# sb-sonata-usbrp.net
KiCad netlist of a schematic drawn in Altium Designer
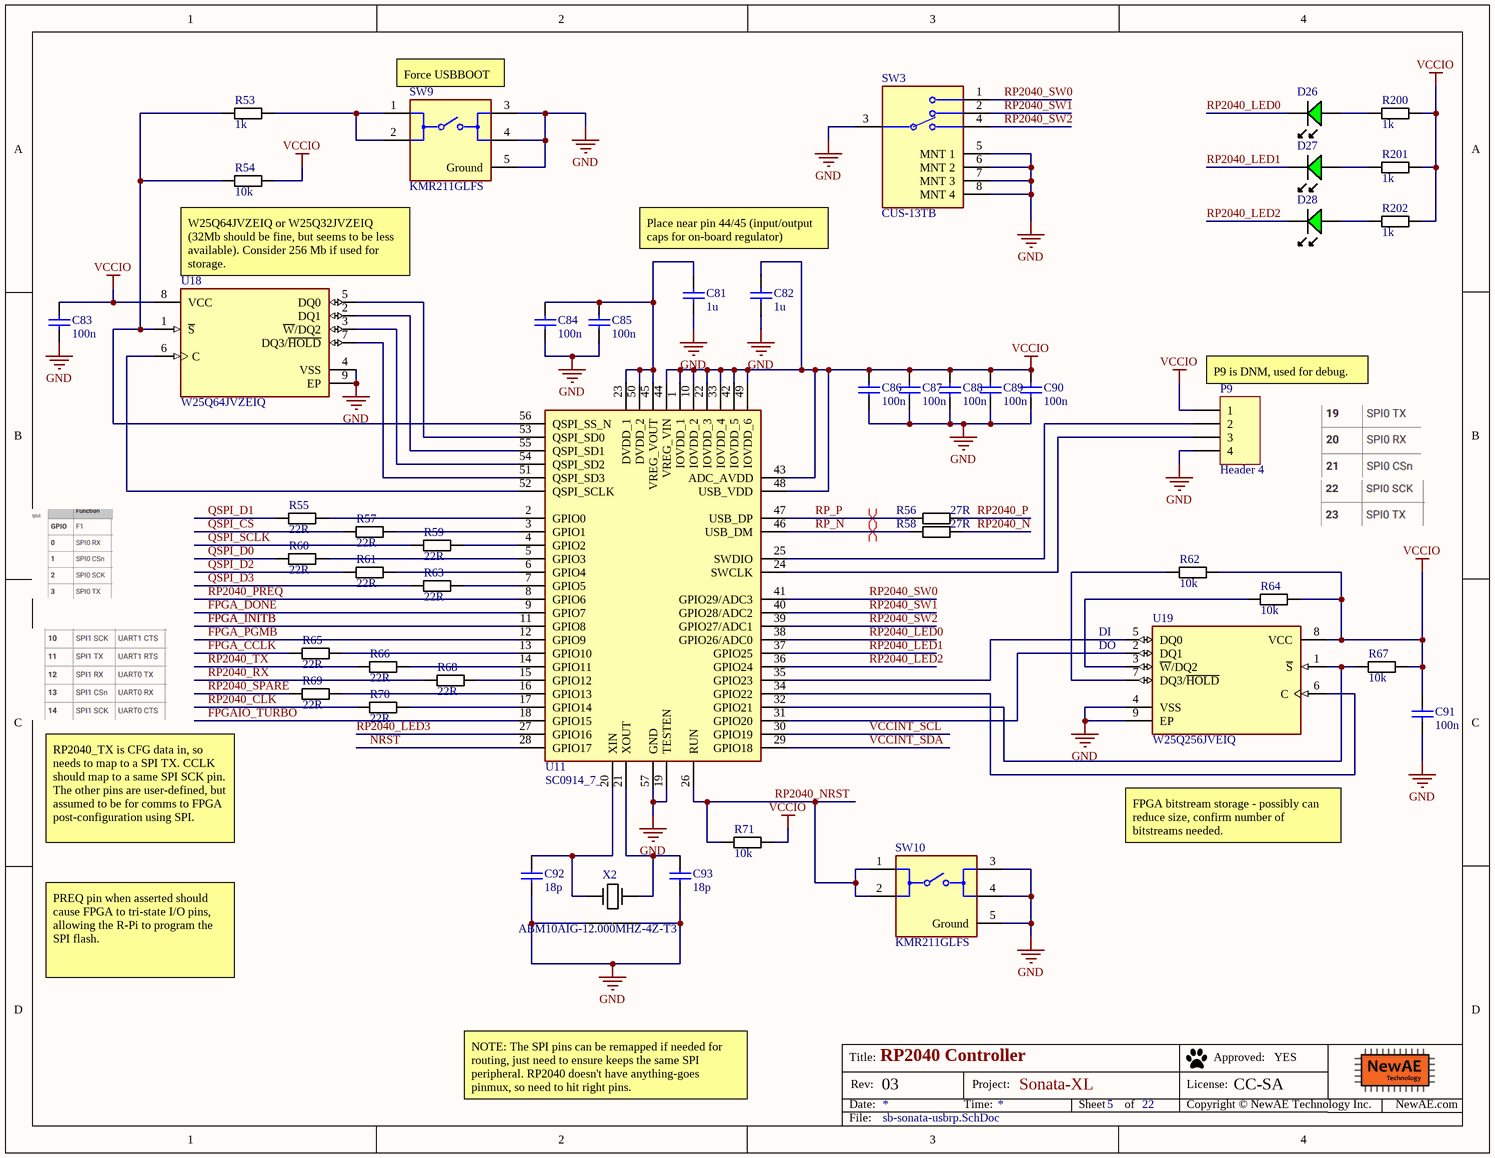
[diagram p0: sb-sonata-usbrp.SchDoc]

(export (version "E")
  (design (tool "Eeschema 10.0.6"))
  (components
    (comp (ref "C81")
      (value "1u")
      (footprint "CAPC0603_M")
      (description "1u, 0603, 50V")
      (fields (field (name "PART NUMBER") "CCHIP-1u-0603"))
      (libsource (lib "NewAE_AltiumLib") (part "CAP"))
    )
    (comp (ref "C82")
      (value "1u")
      (footprint "CAPC0603_M")
      (description "1u, 0603, 50V")
      (fields (field (name "PART NUMBER") "CCHIP-1u-0603"))
      (libsource (lib "NewAE_AltiumLib") (part "CAP"))
    )
    (comp (ref "C83")
      (value "100n")
      (footprint "CAPC0402_M")
      (description "100n, 0402")
      (fields (field (name "PART NUMBER") "CCHIP-100n-0402"))
      (libsource (lib "NewAE_AltiumLib") (part "CAP"))
    )
    (comp (ref "C84")
      (value "100n")
      (footprint "CAPC0402_M")
      (description "100n, 0402")
      (fields (field (name "PART NUMBER") "CCHIP-100n-0402"))
      (libsource (lib "NewAE_AltiumLib") (part "CAP"))
    )
    (comp (ref "C85")
      (value "100n")
      (footprint "CAPC0402_M")
      (description "100n, 0402")
      (fields (field (name "PART NUMBER") "CCHIP-100n-0402"))
      (libsource (lib "NewAE_AltiumLib") (part "CAP"))
    )
    (comp (ref "C86")
      (value "100n")
      (footprint "CAPC0402_M")
      (description "100n, 0402")
      (fields (field (name "PART NUMBER") "CCHIP-100n-0402"))
      (libsource (lib "NewAE_AltiumLib") (part "CAP"))
    )
    (comp (ref "C87")
      (value "100n")
      (footprint "CAPC0402_M")
      (description "100n, 0402")
      (fields (field (name "PART NUMBER") "CCHIP-100n-0402"))
      (libsource (lib "NewAE_AltiumLib") (part "CAP"))
    )
    (comp (ref "C88")
      (value "100n")
      (footprint "CAPC0402_M")
      (description "100n, 0402")
      (fields (field (name "PART NUMBER") "CCHIP-100n-0402"))
      (libsource (lib "NewAE_AltiumLib") (part "CAP"))
    )
    (comp (ref "C89")
      (value "100n")
      (footprint "CAPC0402_M")
      (description "100n, 0402")
      (fields (field (name "PART NUMBER") "CCHIP-100n-0402"))
      (libsource (lib "NewAE_AltiumLib") (part "CAP"))
    )
    (comp (ref "C90")
      (value "100n")
      (footprint "CAPC0402_M")
      (description "100n, 0402")
      (fields (field (name "PART NUMBER") "CCHIP-100n-0402"))
      (libsource (lib "NewAE_AltiumLib") (part "CAP"))
    )
    (comp (ref "C91")
      (value "100n")
      (footprint "CAPC0402_M")
      (description "100n, 0402")
      (fields (field (name "PART NUMBER") "CCHIP-100n-0402"))
      (libsource (lib "NewAE_AltiumLib") (part "CAP"))
    )
    (comp (ref "C92")
      (value "18p")
      (footprint "CAPC0402_M")
      (description "18p, 0402")
      (fields (field (name "PART NUMBER") "CCHIP-18p-0402"))
      (libsource (lib "NewAE_AltiumLib") (part "CAP"))
    )
    (comp (ref "C93")
      (value "18p")
      (footprint "CAPC0402_M")
      (description "18p, 0402")
      (fields (field (name "PART NUMBER") "CCHIP-18p-0402"))
      (libsource (lib "NewAE_AltiumLib") (part "CAP"))
    )
    (comp (ref "D26")
      (value "LED, 0603, Green")
      (footprint "LED-0603-GREEN")
      (description "Chip LED, Green")
      (fields (field (name "PART NUMBER") "LEDCHIP_0603_GREEN"))
      (libsource (lib "NewAE_AltiumLib") (part "LED_GREEN"))
    )
    (comp (ref "D27")
      (value "LED, 0603, Green")
      (footprint "LED-0603-GREEN")
      (description "Chip LED, Green")
      (fields (field (name "PART NUMBER") "LEDCHIP_0603_GREEN"))
      (libsource (lib "NewAE_AltiumLib") (part "LED_GREEN"))
    )
    (comp (ref "D28")
      (value "LED, 0603, Green")
      (footprint "LED-0603-GREEN")
      (description "Chip LED, Green")
      (fields (field (name "PART NUMBER") "LEDCHIP_0603_GREEN"))
      (libsource (lib "NewAE_AltiumLib") (part "LED_GREEN"))
    )
    (comp (ref "P9")
      (value "Header 4")
      (footprint "HDR1X4")
      (description "Header, 4-Pin")
      (fields (field (name "PUBLISHER") "Altium Limited"))
      (libsource (lib "Miscellaneous Connectors") (part "Header 4"))
    )
    (comp (ref "R53")
      (value "1k")
      (footprint "RESC1005X40N")
      (description "1k res, 0402, 1%, 1/16W")
      (fields (field (name "PART NUMBER") "RCHIP-1K-0402") (field (name "TOLERANCE") "1%"))
      (libsource (lib "NewAE_AltiumLib") (part "RES-EU"))
    )
    (comp (ref "R54")
      (value "10k")
      (footprint "RESC1005X40N")
      (description "10k res, 0402, 1%, 1/16W")
      (fields (field (name "PART NUMBER") "RCHIP-10K-0402") (field (name "TOLERANCE") "1%"))
      (libsource (lib "") (part "RES-EU_1"))
    )
    (comp (ref "R55")
      (value "22R")
      (footprint "RESC1005X40N")
      (description "22R res, 0402, 1%, 1/16W")
      (fields (field (name "PART NUMBER") "RCHIP-22R-0402") (field (name "TOLERANCE") "1%"))
      (libsource (lib "NewAE_AltiumLib") (part "RES-EU"))
    )
    (comp (ref "R56")
      (value "27R")
      (footprint "RESC1005X40N")
      (description "27R res, 0402, 1%, 1/16W")
      (fields (field (name "PART NUMBER") "RCHIP-27R-0402") (field (name "TOLERANCE") "1%"))
      (libsource (lib "") (part "RES-EU_1"))
    )
    (comp (ref "R57")
      (value "22R")
      (footprint "RESC1005X40N")
      (description "22R res, 0402, 1%, 1/16W")
      (fields (field (name "PART NUMBER") "RCHIP-22R-0402") (field (name "TOLERANCE") "1%"))
      (libsource (lib "NewAE_AltiumLib") (part "RES-EU"))
    )
    (comp (ref "R58")
      (value "27R")
      (footprint "RESC1005X40N")
      (description "27R res, 0402, 1%, 1/16W")
      (fields (field (name "PART NUMBER") "RCHIP-27R-0402") (field (name "TOLERANCE") "1%"))
      (libsource (lib "") (part "RES-EU_1"))
    )
    (comp (ref "R59")
      (value "22R")
      (footprint "RESC1005X40N")
      (description "22R res, 0402, 1%, 1/16W")
      (fields (field (name "PART NUMBER") "RCHIP-22R-0402") (field (name "TOLERANCE") "1%"))
      (libsource (lib "NewAE_AltiumLib") (part "RES-EU"))
    )
    (comp (ref "R60")
      (value "22R")
      (footprint "RESC1005X40N")
      (description "22R res, 0402, 1%, 1/16W")
      (fields (field (name "PART NUMBER") "RCHIP-22R-0402") (field (name "TOLERANCE") "1%"))
      (libsource (lib "NewAE_AltiumLib") (part "RES-EU"))
    )
    (comp (ref "R61")
      (value "22R")
      (footprint "RESC1005X40N")
      (description "22R res, 0402, 1%, 1/16W")
      (fields (field (name "PART NUMBER") "RCHIP-22R-0402") (field (name "TOLERANCE") "1%"))
      (libsource (lib "NewAE_AltiumLib") (part "RES-EU"))
    )
    (comp (ref "R62")
      (value "10k")
      (footprint "RESC1005X40N")
      (description "10k res, 0402, 1%, 1/16W")
      (fields (field (name "PART NUMBER") "RCHIP-10K-0402") (field (name "TOLERANCE") "1%"))
      (libsource (lib "") (part "RES-EU_1"))
    )
    (comp (ref "R63")
      (value "22R")
      (footprint "RESC1005X40N")
      (description "22R res, 0402, 1%, 1/16W")
      (fields (field (name "PART NUMBER") "RCHIP-22R-0402") (field (name "TOLERANCE") "1%"))
      (libsource (lib "NewAE_AltiumLib") (part "RES-EU"))
    )
    (comp (ref "R64")
      (value "10k")
      (footprint "RESC1005X40N")
      (description "10k res, 0402, 1%, 1/16W")
      (fields (field (name "PART NUMBER") "RCHIP-10K-0402") (field (name "TOLERANCE") "1%"))
      (libsource (lib "") (part "RES-EU_1"))
    )
    (comp (ref "R65")
      (value "22R")
      (footprint "RESC1005X40N")
      (description "22R res, 0402, 1%, 1/16W")
      (fields (field (name "PART NUMBER") "RCHIP-22R-0402") (field (name "TOLERANCE") "1%"))
      (libsource (lib "NewAE_AltiumLib") (part "RES-EU"))
    )
    (comp (ref "R66")
      (value "22R")
      (footprint "RESC1005X40N")
      (description "22R res, 0402, 1%, 1/16W")
      (fields (field (name "PART NUMBER") "RCHIP-22R-0402") (field (name "TOLERANCE") "1%"))
      (libsource (lib "NewAE_AltiumLib") (part "RES-EU"))
    )
    (comp (ref "R67")
      (value "10k")
      (footprint "RESC1005X40N")
      (description "10k res, 0402, 1%, 1/16W")
      (fields (field (name "PART NUMBER") "RCHIP-10K-0402") (field (name "TOLERANCE") "1%"))
      (libsource (lib "NewAE_AltiumLib") (part "RES-EU"))
    )
    (comp (ref "R68")
      (value "22R")
      (footprint "RESC1005X40N")
      (description "22R res, 0402, 1%, 1/16W")
      (fields (field (name "PART NUMBER") "RCHIP-22R-0402") (field (name "TOLERANCE") "1%"))
      (libsource (lib "NewAE_AltiumLib") (part "RES-EU"))
    )
    (comp (ref "R69")
      (value "22R")
      (footprint "RESC1005X40N")
      (description "22R res, 0402, 1%, 1/16W")
      (fields (field (name "PART NUMBER") "RCHIP-22R-0402") (field (name "TOLERANCE") "1%"))
      (libsource (lib "NewAE_AltiumLib") (part "RES-EU"))
    )
    (comp (ref "R70")
      (value "22R")
      (footprint "RESC1005X40N")
      (description "22R res, 0402, 1%, 1/16W")
      (fields (field (name "PART NUMBER") "RCHIP-22R-0402") (field (name "TOLERANCE") "1%"))
      (libsource (lib "NewAE_AltiumLib") (part "RES-EU"))
    )
    (comp (ref "R71")
      (value "10k")
      (footprint "RESC1005X40N")
      (description "10k res, 0402, 1%, 1/16W")
      (fields (field (name "PART NUMBER") "RCHIP-10K-0402") (field (name "TOLERANCE") "1%"))
      (libsource (lib "NewAE_AltiumLib") (part "RES-EU"))
    )
    (comp (ref "R200")
      (value "1k")
      (footprint "RESC1005X40N")
      (description "1k res, 0402, 1%, 1/16W")
      (fields (field (name "PART NUMBER") "RCHIP-1K-0402") (field (name "TOLERANCE") "1%"))
      (libsource (lib "NewAE_AltiumLib") (part "RES-EU"))
    )
    (comp (ref "R201")
      (value "1k")
      (footprint "RESC1005X40N")
      (description "1k res, 0402, 1%, 1/16W")
      (fields (field (name "PART NUMBER") "RCHIP-1K-0402") (field (name "TOLERANCE") "1%"))
      (libsource (lib "NewAE_AltiumLib") (part "RES-EU"))
    )
    (comp (ref "R202")
      (value "1k")
      (footprint "RESC1005X40N")
      (description "1k res, 0402, 1%, 1/16W")
      (fields (field (name "PART NUMBER") "RCHIP-1K-0402") (field (name "TOLERANCE") "1%"))
      (libsource (lib "NewAE_AltiumLib") (part "RES-EU"))
    )
    (comp (ref "SW3")
      (value "CUS-13TB")
      (footprint "FP-CUS-13TB-MFG")
      (description "SWITCH SLIDE SP3T 300MA 4V")
      (libsource (lib "Altium Content Vault") (part "47bcb96ef67674530f45e4053201745"))
    )
    (comp (ref "SW9")
      (value "KMR211GLFS")
      (footprint "FP-KMR211GLFS-MFG")
      (description "SWITCH TACTILE SPST-NO 0.05A 32V")
      (libsource (lib "Altium Content Vault") (part "99988cc0f9d3d39bd794ae22da860e5"))
    )
    (comp (ref "SW10")
      (value "KMR211GLFS")
      (footprint "FP-KMR211GLFS-MFG")
      (description "SWITCH TACTILE SPST-NO 0.05A 32V")
      (libsource (lib "Altium Content Vault") (part "99988cc0f9d3d39bd794ae22da860e5"))
    )
    (comp (ref "U11")
      (value "SC0914_7_")
      (footprint "QFN40P700X700X90-57N-D")
      (description "Connector")
      (fields
        (field (name "MANUFACTURER_PART_NUMBER") "SC0914(7)")
        (field (name "MOUSER PART NUMBER") "358-SC09147")
      )
      (libsource (lib "*") (part "SC0914_7_"))
    )
    (comp (ref "U18")
      (value "W25Q64JVZEIQ")
      (footprint "WSON68_Micron")
      (description "IC FLASH 64M SPI 133MHZ 8WPDFN")
      (libsource (lib "") (part "QSPI_WSON_1"))
    )
    (comp (ref "U19")
      (value "W25Q256JVEIQ")
      (footprint "WSON68_Micron")
      (description "IC FLASH 256M SPI 133MHZ 8WPDFN")
      (libsource (lib "NewAE_AltiumLib") (part "QSPI_WSON"))
    )
    (comp (ref "X2")
      (value "ABM10AIG-12.000MHZ-4Z-T3")
      (footprint "2.5x2mm XTAL")
      (description "12MHz, SMD")
      (libsource (lib "NewAE_AltiumLib") (part "XTAL_4PIN_13"))
    )
  )
  (nets
    (net (code "1") (name "/FPGAIO_TURBO") (class "Default")
      (node (ref "U11") (pin "18") (pinfunction "GPIO15_18") (pintype "passive"))
    )
    (net (code "2") (name "/FPGA_CCLK") (class "Default")
      (node (ref "R65") (pin "1") (pinfunction "1_1") (pintype "passive"))
    )
    (net (code "3") (name "/FPGA_DONE") (class "Default")
      (node (ref "U11") (pin "9") (pinfunction "GPIO7_9") (pintype "passive"))
    )
    (net (code "4") (name "/FPGA_INITB") (class "Default")
      (node (ref "U11") (pin "11") (pinfunction "GPIO8_11") (pintype "passive"))
    )
    (net (code "5") (name "/FPGA_PGMB") (class "Default")
      (node (ref "U11") (pin "12") (pinfunction "GPIO9_12") (pintype "passive"))
    )
    (net (code "6") (name "/NRST") (class "Default")
      (node (ref "U11") (pin "28") (pinfunction "GPIO17_28") (pintype "passive"))
    )
    (net (code "7") (name "/QSPI_CS") (class "Default")
      (node (ref "R57") (pin "1") (pinfunction "1_1") (pintype "passive"))
    )
    (net (code "8") (name "/QSPI_D0") (class "Default")
      (node (ref "R60") (pin "1") (pinfunction "1_1") (pintype "passive"))
    )
    (net (code "9") (name "/QSPI_D1") (class "Default")
      (node (ref "R55") (pin "1") (pinfunction "1_1") (pintype "passive"))
    )
    (net (code "10") (name "/QSPI_D2") (class "Default")
      (node (ref "R61") (pin "1") (pinfunction "1_1") (pintype "passive"))
    )
    (net (code "11") (name "/QSPI_D3") (class "Default")
      (node (ref "R63") (pin "1") (pinfunction "1_1") (pintype "passive"))
    )
    (net (code "12") (name "/QSPI_SCLK") (class "Default")
      (node (ref "R59") (pin "1") (pinfunction "1_1") (pintype "passive"))
    )
    (net (code "13") (name "/RP2040_CLK") (class "Default")
      (node (ref "R70") (pin "1") (pinfunction "1_1") (pintype "passive"))
    )
    (net (code "14") (name "/RP2040_LED0") (class "Default")
      (node (ref "D26") (pin "K") (pinfunction "K_K") (pintype "passive"))
      (node (ref "U11") (pin "38") (pinfunction "GPIO26/ADC0_38") (pintype "passive"))
    )
    (net (code "15") (name "/RP2040_LED1") (class "Default")
      (node (ref "D27") (pin "K") (pinfunction "K_K") (pintype "passive"))
      (node (ref "U11") (pin "37") (pinfunction "GPIO25_37") (pintype "passive"))
    )
    (net (code "16") (name "/RP2040_LED2") (class "Default")
      (node (ref "D28") (pin "K") (pinfunction "K_K") (pintype "passive"))
      (node (ref "U11") (pin "36") (pinfunction "GPIO24_36") (pintype "passive"))
    )
    (net (code "17") (name "/RP2040_LED3") (class "Default")
      (node (ref "U11") (pin "27") (pinfunction "GPIO16_27") (pintype "passive"))
    )
    (net (code "18") (name "/RP2040_N") (class "Default")
      (node (ref "R58") (pin "1") (pinfunction "1_1") (pintype "passive"))
    )
    (net (code "19") (name "/RP2040_NRST") (class "Default")
      (node (ref "R71") (pin "1") (pinfunction "1_1") (pintype "passive"))
      (node (ref "SW10") (pin "1") (pinfunction "1_1") (pintype "passive"))
      (node (ref "SW10") (pin "2") (pinfunction "2_2") (pintype "passive"))
      (node (ref "U11") (pin "26") (pinfunction "RUN_26") (pintype "passive"))
    )
    (net (code "20") (name "/RP2040_P") (class "Default")
      (node (ref "R56") (pin "1") (pinfunction "1_1") (pintype "passive"))
    )
    (net (code "21") (name "/RP2040_PREQ") (class "Default")
      (node (ref "U11") (pin "8") (pinfunction "GPIO6_8") (pintype "passive"))
    )
    (net (code "22") (name "/RP2040_RX") (class "Default")
      (node (ref "R68") (pin "1") (pinfunction "1_1") (pintype "passive"))
    )
    (net (code "23") (name "/RP2040_SPARE") (class "Default")
      (node (ref "R69") (pin "1") (pinfunction "1_1") (pintype "passive"))
    )
    (net (code "24") (name "/RP2040_SW0") (class "Default")
      (node (ref "SW3") (pin "1") (pinfunction "1_1") (pintype "passive"))
      (node (ref "U11") (pin "41") (pinfunction "GPIO29/ADC3_41") (pintype "passive"))
    )
    (net (code "25") (name "/RP2040_SW1") (class "Default")
      (node (ref "SW3") (pin "2") (pinfunction "2_2") (pintype "passive"))
      (node (ref "U11") (pin "40") (pinfunction "GPIO28/ADC2_40") (pintype "passive"))
    )
    (net (code "26") (name "/RP2040_SW2") (class "Default")
      (node (ref "SW3") (pin "4") (pinfunction "4_4") (pintype "passive"))
      (node (ref "U11") (pin "39") (pinfunction "GPIO27/ADC1_39") (pintype "passive"))
    )
    (net (code "27") (name "/RP2040_TX") (class "Default")
      (node (ref "R66") (pin "1") (pinfunction "1_1") (pintype "passive"))
    )
    (net (code "28") (name "/RP_N") (class "Default")
      (node (ref "R58") (pin "2") (pinfunction "2_2") (pintype "passive"))
      (node (ref "U11") (pin "46") (pinfunction "USB_DM_46") (pintype "passive"))
    )
    (net (code "29") (name "/RP_P") (class "Default")
      (node (ref "R56") (pin "2") (pinfunction "2_2") (pintype "passive"))
      (node (ref "U11") (pin "47") (pinfunction "USB_DP_47") (pintype "passive"))
    )
    (net (code "30") (name "/VCCINT_SCL") (class "Default")
      (node (ref "U11") (pin "30") (pinfunction "GPIO19_30") (pintype "passive"))
    )
    (net (code "31") (name "/VCCINT_SDA") (class "Default")
      (node (ref "U11") (pin "29") (pinfunction "GPIO18_29") (pintype "passive"))
    )
    (net (code "32") (name "GND") (class "Default")
      (node (ref "C81") (pin "2") (pinfunction "2_2") (pintype "passive"))
      (node (ref "C82") (pin "2") (pinfunction "2_2") (pintype "passive"))
      (node (ref "C83") (pin "2") (pinfunction "2_2") (pintype "passive"))
      (node (ref "C84") (pin "2") (pinfunction "2_2") (pintype "passive"))
      (node (ref "C85") (pin "2") (pinfunction "2_2") (pintype "passive"))
      (node (ref "C86") (pin "2") (pinfunction "2_2") (pintype "passive"))
      (node (ref "C87") (pin "2") (pinfunction "2_2") (pintype "passive"))
      (node (ref "C88") (pin "2") (pinfunction "2_2") (pintype "passive"))
      (node (ref "C89") (pin "2") (pinfunction "2_2") (pintype "passive"))
      (node (ref "C90") (pin "2") (pinfunction "2_2") (pintype "passive"))
      (node (ref "C91") (pin "2") (pinfunction "2_2") (pintype "passive"))
      (node (ref "C92") (pin "2") (pinfunction "2_2") (pintype "passive"))
      (node (ref "C93") (pin "2") (pinfunction "2_2") (pintype "passive"))
      (node (ref "P9") (pin "4") (pinfunction "4_4") (pintype "passive"))
      (node (ref "SW10") (pin "3") (pinfunction "3_3") (pintype "passive"))
      (node (ref "SW10") (pin "4") (pinfunction "4_4") (pintype "passive"))
      (node (ref "SW10") (pin "5") (pinfunction "Ground_5") (pintype "power_in"))
      (node (ref "SW3") (pin "3") (pinfunction "C_3") (pintype "passive"))
      (node (ref "SW3") (pin "5") (pinfunction "MNT_1_5") (pintype "passive"))
      (node (ref "SW3") (pin "6") (pinfunction "MNT_2_6") (pintype "passive"))
      (node (ref "SW3") (pin "7") (pinfunction "MNT_3_7") (pintype "passive"))
      (node (ref "SW3") (pin "8") (pinfunction "MNT_4_8") (pintype "passive"))
      (node (ref "SW9") (pin "3") (pinfunction "3_3") (pintype "passive"))
      (node (ref "SW9") (pin "4") (pinfunction "4_4") (pintype "passive"))
      (node (ref "SW9") (pin "5") (pinfunction "Ground_5") (pintype "power_in"))
      (node (ref "U11") (pin "19") (pinfunction "TESTEN_19") (pintype "passive"))
      (node (ref "U11") (pin "57") (pinfunction "GND_57") (pintype "passive"))
      (node (ref "U18") (pin "4") (pinfunction "VSS_4") (pintype "power_in"))
      (node (ref "U18") (pin "9") (pinfunction "EP_9") (pintype "power_in"))
      (node (ref "U19") (pin "4") (pinfunction "VSS_4") (pintype "power_in"))
      (node (ref "U19") (pin "9") (pinfunction "EP_9") (pintype "power_in"))
      (node (ref "X2") (pin "2") (pinfunction "GND_2") (pintype "power_in"))
      (node (ref "X2") (pin "4") (pinfunction "GND_4") (pintype "power_in"))
    )
    (net (code "33") (name "Net-(D26-PadA)") (class "Default")
      (node (ref "D26") (pin "A") (pinfunction "A_A") (pintype "passive"))
      (node (ref "R200") (pin "1") (pinfunction "1_1") (pintype "passive"))
    )
    (net (code "34") (name "Net-(D27-PadA)") (class "Default")
      (node (ref "D27") (pin "A") (pinfunction "A_A") (pintype "passive"))
      (node (ref "R201") (pin "1") (pinfunction "1_1") (pintype "passive"))
    )
    (net (code "35") (name "Net-(D28-PadA)") (class "Default")
      (node (ref "D28") (pin "A") (pinfunction "A_A") (pintype "passive"))
      (node (ref "R202") (pin "1") (pinfunction "1_1") (pintype "passive"))
    )
    (net (code "36") (name "Net-(R53-Pad2)") (class "Default")
      (node (ref "R53") (pin "2") (pinfunction "2_2") (pintype "passive"))
      (node (ref "SW9") (pin "1") (pinfunction "1_1") (pintype "passive"))
      (node (ref "SW9") (pin "2") (pinfunction "2_2") (pintype "passive"))
    )
    (net (code "37") (name "Net-(U11-DVDD_1)") (class "Default")
      (node (ref "C81") (pin "1") (pinfunction "1_1") (pintype "passive"))
      (node (ref "C84") (pin "1") (pinfunction "1_1") (pintype "passive"))
      (node (ref "C85") (pin "1") (pinfunction "1_1") (pintype "passive"))
      (node (ref "U11") (pin "23") (pinfunction "DVDD_1_23") (pintype "passive"))
      (node (ref "U11") (pin "45") (pinfunction "VREG_VOUT_45") (pintype "passive"))
      (node (ref "U11") (pin "50") (pinfunction "DVDD_2_50") (pintype "passive"))
    )
    (net (code "38") (name "Net-(U11-GPIO0)") (class "Default")
      (node (ref "R55") (pin "2") (pinfunction "2_2") (pintype "passive"))
      (node (ref "U11") (pin "2") (pinfunction "GPIO0_2") (pintype "passive"))
    )
    (net (code "39") (name "Net-(U11-GPIO1)") (class "Default")
      (node (ref "R57") (pin "2") (pinfunction "2_2") (pintype "passive"))
      (node (ref "U11") (pin "3") (pinfunction "GPIO1_3") (pintype "passive"))
    )
    (net (code "40") (name "Net-(U11-GPIO2)") (class "Default")
      (node (ref "R59") (pin "2") (pinfunction "2_2") (pintype "passive"))
      (node (ref "U11") (pin "4") (pinfunction "GPIO2_4") (pintype "passive"))
    )
    (net (code "41") (name "Net-(U11-GPIO3)") (class "Default")
      (node (ref "R60") (pin "2") (pinfunction "2_2") (pintype "passive"))
      (node (ref "U11") (pin "5") (pinfunction "GPIO3_5") (pintype "passive"))
    )
    (net (code "42") (name "Net-(U11-GPIO4)") (class "Default")
      (node (ref "R61") (pin "2") (pinfunction "2_2") (pintype "passive"))
      (node (ref "U11") (pin "6") (pinfunction "GPIO4_6") (pintype "passive"))
    )
    (net (code "43") (name "Net-(U11-GPIO5)") (class "Default")
      (node (ref "R63") (pin "2") (pinfunction "2_2") (pintype "passive"))
      (node (ref "U11") (pin "7") (pinfunction "GPIO5_7") (pintype "passive"))
    )
    (net (code "44") (name "Net-(U11-GPIO10)") (class "Default")
      (node (ref "R65") (pin "2") (pinfunction "2_2") (pintype "passive"))
      (node (ref "U11") (pin "13") (pinfunction "GPIO10_13") (pintype "passive"))
    )
    (net (code "45") (name "Net-(U11-GPIO11)") (class "Default")
      (node (ref "R66") (pin "2") (pinfunction "2_2") (pintype "passive"))
      (node (ref "U11") (pin "14") (pinfunction "GPIO11_14") (pintype "passive"))
    )
    (net (code "46") (name "Net-(U11-GPIO12)") (class "Default")
      (node (ref "R68") (pin "2") (pinfunction "2_2") (pintype "passive"))
      (node (ref "U11") (pin "15") (pinfunction "GPIO12_15") (pintype "passive"))
    )
    (net (code "47") (name "Net-(U11-GPIO13)") (class "Default")
      (node (ref "R69") (pin "2") (pinfunction "2_2") (pintype "passive"))
      (node (ref "U11") (pin "16") (pinfunction "GPIO13_16") (pintype "passive"))
    )
    (net (code "48") (name "Net-(U11-GPIO14)") (class "Default")
      (node (ref "R70") (pin "2") (pinfunction "2_2") (pintype "passive"))
      (node (ref "U11") (pin "17") (pinfunction "GPIO14_17") (pintype "passive"))
    )
    (net (code "49") (name "Net-(U11-GPIO20)") (class "Default")
      (node (ref "U11") (pin "31") (pinfunction "GPIO20_31") (pintype "passive"))
      (node (ref "U19") (pin "2") (pinfunction "DQ1_2") (pintype "bidirectional"))
    )
    (net (code "50") (name "Net-(U11-GPIO21)") (class "Default")
      (node (ref "R67") (pin "1") (pinfunction "1_1") (pintype "passive"))
      (node (ref "U11") (pin "32") (pinfunction "GPIO21_32") (pintype "passive"))
      (node (ref "U19") (pin "1") (pinfunction "~{S}_1") (pintype "input"))
    )
    (net (code "51") (name "Net-(U11-GPIO22)") (class "Default")
      (node (ref "U11") (pin "34") (pinfunction "GPIO22_34") (pintype "passive"))
      (node (ref "U19") (pin "6") (pinfunction "C_6") (pintype "input"))
    )
    (net (code "52") (name "Net-(U11-GPIO23)") (class "Default")
      (node (ref "U11") (pin "35") (pinfunction "GPIO23_35") (pintype "passive"))
      (node (ref "U19") (pin "5") (pinfunction "DQ0_5") (pintype "bidirectional"))
    )
    (net (code "53") (name "Net-(U11-QSPI_SCLK)") (class "Default")
      (node (ref "U11") (pin "52") (pinfunction "QSPI_SCLK_52") (pintype "passive"))
      (node (ref "U18") (pin "6") (pinfunction "C_6") (pintype "input"))
    )
    (net (code "54") (name "Net-(U11-QSPI_SD0)") (class "Default")
      (node (ref "U11") (pin "53") (pinfunction "QSPI_SD0_53") (pintype "passive"))
      (node (ref "U18") (pin "5") (pinfunction "DQ0_5") (pintype "bidirectional"))
    )
    (net (code "55") (name "Net-(U11-QSPI_SD1)") (class "Default")
      (node (ref "U11") (pin "55") (pinfunction "QSPI_SD1_55") (pintype "passive"))
      (node (ref "U18") (pin "2") (pinfunction "DQ1_2") (pintype "bidirectional"))
    )
    (net (code "56") (name "Net-(U11-QSPI_SD2)") (class "Default")
      (node (ref "U11") (pin "54") (pinfunction "QSPI_SD2_54") (pintype "passive"))
      (node (ref "U18") (pin "3") (pinfunction "~{W}/DQ2_3") (pintype "bidirectional"))
    )
    (net (code "57") (name "Net-(U11-QSPI_SD3)") (class "Default")
      (node (ref "U11") (pin "51") (pinfunction "QSPI_SD3_51") (pintype "passive"))
      (node (ref "U18") (pin "7") (pinfunction "DQ3/~{HOLD}_7") (pintype "bidirectional"))
    )
    (net (code "58") (name "Net-(U11-QSPI_SS_N)") (class "Default")
      (node (ref "R53") (pin "1") (pinfunction "1_1") (pintype "passive"))
      (node (ref "R54") (pin "2") (pinfunction "2_2") (pintype "passive"))
      (node (ref "U11") (pin "56") (pinfunction "QSPI_SS_N_56") (pintype "passive"))
      (node (ref "U18") (pin "1") (pinfunction "~{S}_1") (pintype "input"))
    )
    (net (code "59") (name "Net-(U11-SWCLK)") (class "Default")
      (node (ref "P9") (pin "3") (pinfunction "3_3") (pintype "passive"))
      (node (ref "U11") (pin "24") (pinfunction "SWCLK_24") (pintype "passive"))
    )
    (net (code "60") (name "Net-(U11-SWDIO)") (class "Default")
      (node (ref "P9") (pin "2") (pinfunction "2_2") (pintype "passive"))
      (node (ref "U11") (pin "25") (pinfunction "SWDIO_25") (pintype "passive"))
    )
    (net (code "61") (name "Net-(U11-XIN)") (class "Default")
      (node (ref "C92") (pin "1") (pinfunction "1_1") (pintype "passive"))
      (node (ref "U11") (pin "20") (pinfunction "XIN_20") (pintype "passive"))
      (node (ref "X2") (pin "1") (pinfunction "IN_1") (pintype "passive"))
    )
    (net (code "62") (name "Net-(U11-XOUT)") (class "Default")
      (node (ref "C93") (pin "1") (pinfunction "1_1") (pintype "passive"))
      (node (ref "U11") (pin "21") (pinfunction "XOUT_21") (pintype "passive"))
      (node (ref "X2") (pin "3") (pinfunction "OUT_3") (pintype "passive"))
    )
    (net (code "63") (name "Net-(U19-DQ3{slash}~{HOLD})") (class "Default")
      (node (ref "R62") (pin "2") (pinfunction "2_2") (pintype "passive"))
      (node (ref "U19") (pin "7") (pinfunction "DQ3/~{HOLD}_7") (pintype "bidirectional"))
    )
    (net (code "64") (name "Net-(U19-~{W}{slash}DQ2)") (class "Default")
      (node (ref "R64") (pin "2") (pinfunction "2_2") (pintype "passive"))
      (node (ref "U19") (pin "3") (pinfunction "~{W}/DQ2_3") (pintype "bidirectional"))
    )
    (net (code "65") (name "VCCIO") (class "Default")
      (node (ref "C82") (pin "1") (pinfunction "1_1") (pintype "passive"))
      (node (ref "C83") (pin "1") (pinfunction "1_1") (pintype "passive"))
      (node (ref "C86") (pin "1") (pinfunction "1_1") (pintype "passive"))
      (node (ref "C87") (pin "1") (pinfunction "1_1") (pintype "passive"))
      (node (ref "C88") (pin "1") (pinfunction "1_1") (pintype "passive"))
      (node (ref "C89") (pin "1") (pinfunction "1_1") (pintype "passive"))
      (node (ref "C90") (pin "1") (pinfunction "1_1") (pintype "passive"))
      (node (ref "C91") (pin "1") (pinfunction "1_1") (pintype "passive"))
      (node (ref "P9") (pin "1") (pinfunction "1_1") (pintype "passive"))
      (node (ref "R200") (pin "2") (pinfunction "2_2") (pintype "passive"))
      (node (ref "R201") (pin "2") (pinfunction "2_2") (pintype "passive"))
      (node (ref "R202") (pin "2") (pinfunction "2_2") (pintype "passive"))
      (node (ref "R54") (pin "1") (pinfunction "1_1") (pintype "passive"))
      (node (ref "R62") (pin "1") (pinfunction "1_1") (pintype "passive"))
      (node (ref "R64") (pin "1") (pinfunction "1_1") (pintype "passive"))
      (node (ref "R67") (pin "2") (pinfunction "2_2") (pintype "passive"))
      (node (ref "R71") (pin "2") (pinfunction "2_2") (pintype "passive"))
      (node (ref "U11") (pin "1") (pinfunction "IOVDD_1_1") (pintype "passive"))
      (node (ref "U11") (pin "10") (pinfunction "IOVDD_2_10") (pintype "passive"))
      (node (ref "U11") (pin "22") (pinfunction "IOVDD_3_22") (pintype "passive"))
      (node (ref "U11") (pin "33") (pinfunction "IOVDD_4_33") (pintype "passive"))
      (node (ref "U11") (pin "42") (pinfunction "IOVDD_5_42") (pintype "passive"))
      (node (ref "U11") (pin "43") (pinfunction "ADC_AVDD_43") (pintype "passive"))
      (node (ref "U11") (pin "44") (pinfunction "VREG_VIN_44") (pintype "passive"))
      (node (ref "U11") (pin "48") (pinfunction "USB_VDD_48") (pintype "passive"))
      (node (ref "U11") (pin "49") (pinfunction "IOVDD_6_49") (pintype "passive"))
      (node (ref "U18") (pin "8") (pinfunction "VCC_8") (pintype "power_in"))
      (node (ref "U19") (pin "8") (pinfunction "VCC_8") (pintype "power_in"))
    )
  )
)
